# sc01a-breakout-board.net
KiCad netlist of a schematic drawn in EAGLE
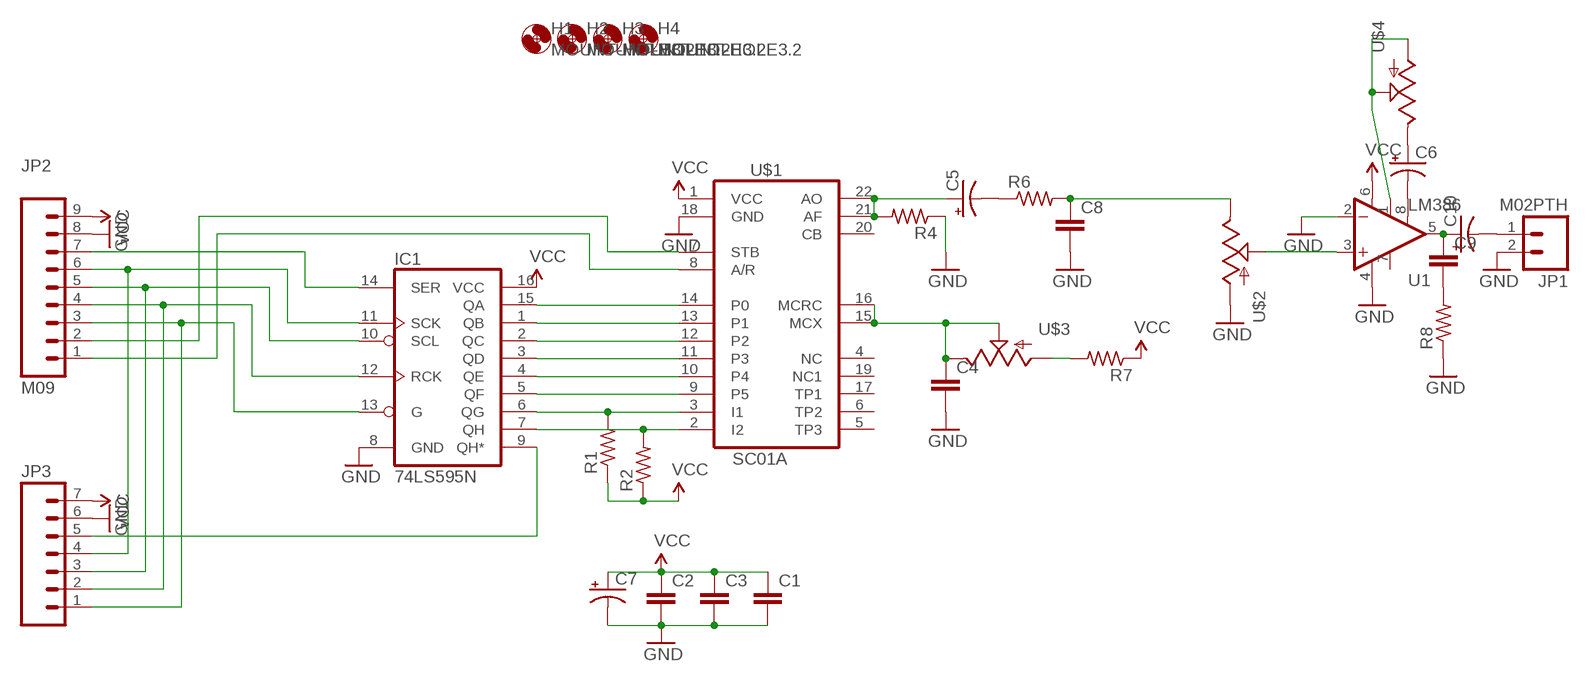
[diagram p0: schematic, sheet 1]

(export (version "E")
  (design (tool "Eeschema 10.0.6"))
  (components
    (comp (ref "C1")
      (value "CAPEZ")
      (footprint "eagle-import:CAP-PTH-SMALLEZ")
      (libsource (lib "eagle-import") (part "CAPEZ"))
    )
    (comp (ref "C2")
      (value "CAPEZ")
      (footprint "eagle-import:CAP-PTH-SMALLEZ")
      (libsource (lib "eagle-import") (part "CAPEZ"))
    )
    (comp (ref "C3")
      (value "CAPEZ")
      (footprint "eagle-import:CAP-PTH-SMALLEZ")
      (libsource (lib "eagle-import") (part "CAPEZ"))
    )
    (comp (ref "C4")
      (value "CAPEZ")
      (footprint "eagle-import:CAP-PTH-SMALLEZ")
      (libsource (lib "eagle-import") (part "CAPEZ"))
    )
    (comp (ref "C5")
      (value "CAP_POLPTH2")
      (footprint "eagle-import:CPOL-RADIAL-10UF-25V")
      (libsource (lib "eagle-import") (part "CAP_POLPTH2"))
    )
    (comp (ref "C6")
      (value "CAP_POLPTH2")
      (footprint "eagle-import:CPOL-RADIAL-10UF-25V")
      (libsource (lib "eagle-import") (part "CAP_POLPTH2"))
    )
    (comp (ref "C7")
      (value "CAP_POLPTH2")
      (footprint "eagle-import:CPOL-RADIAL-10UF-25V")
      (libsource (lib "eagle-import") (part "CAP_POLPTH2"))
    )
    (comp (ref "C8")
      (value "CAPEZ")
      (footprint "eagle-import:CAP-PTH-SMALLEZ")
      (libsource (lib "eagle-import") (part "CAPEZ"))
    )
    (comp (ref "C9")
      (value "CAPEZ")
      (footprint "eagle-import:CAP-PTH-SMALLEZ")
      (libsource (lib "eagle-import") (part "CAPEZ"))
    )
    (comp (ref "C10")
      (value "CAP_POLPTH2")
      (footprint "eagle-import:CPOL-RADIAL-10UF-25V")
      (libsource (lib "eagle-import") (part "CAP_POLPTH2"))
    )
    (comp (ref "H1")
      (value "MOUNT-HOLE3.2")
      (footprint "eagle-import:3,2")
      (libsource (lib "eagle-import") (part "MOUNT-HOLE3.2"))
    )
    (comp (ref "H2")
      (value "MOUNT-HOLE3.2")
      (footprint "eagle-import:3,2")
      (libsource (lib "eagle-import") (part "MOUNT-HOLE3.2"))
    )
    (comp (ref "H3")
      (value "MOUNT-HOLE3.2")
      (footprint "eagle-import:3,2")
      (libsource (lib "eagle-import") (part "MOUNT-HOLE3.2"))
    )
    (comp (ref "H4")
      (value "MOUNT-HOLE3.2")
      (footprint "eagle-import:3,2")
      (libsource (lib "eagle-import") (part "MOUNT-HOLE3.2"))
    )
    (comp (ref "IC1")
      (value "74LS595N")
      (footprint "eagle-import:DIL16")
      (libsource (lib "eagle-import") (part "74595NLS"))
    )
    (comp (ref "JP1")
      (value "M02PTH")
      (footprint "eagle-import:1X02")
      (libsource (lib "eagle-import") (part "M02PTH"))
    )
    (comp (ref "JP2")
      (value "M09")
      (footprint "eagle-import:1X09")
      (libsource (lib "eagle-import") (part "M09"))
    )
    (comp (ref "JP3")
      (value "M07")
      (footprint "eagle-import:1X07")
      (libsource (lib "eagle-import") (part "M07"))
    )
    (comp (ref "R1")
      (value "R-US_0204/5")
      (footprint "eagle-import:0204_5")
      (libsource (lib "eagle-import") (part "R-US_0204/5"))
    )
    (comp (ref "R2")
      (value "R-US_0204/5")
      (footprint "eagle-import:0204_5")
      (libsource (lib "eagle-import") (part "R-US_0204/5"))
    )
    (comp (ref "R4")
      (value "R-US_0204/5")
      (footprint "eagle-import:0204_5")
      (libsource (lib "eagle-import") (part "R-US_0204/5"))
    )
    (comp (ref "R6")
      (value "R-US_0204/5")
      (footprint "eagle-import:0204_5")
      (libsource (lib "eagle-import") (part "R-US_0204/5"))
    )
    (comp (ref "R7")
      (value "R-US_0204/5")
      (footprint "eagle-import:0204_5")
      (libsource (lib "eagle-import") (part "R-US_0204/5"))
    )
    (comp (ref "R8")
      (value "R-US_0204/5")
      (footprint "eagle-import:0204_5")
      (libsource (lib "eagle-import") (part "R-US_0204/5"))
    )
    (comp (ref "U$1")
      (value "SC01A")
      (footprint "eagle-import:22PDIP4")
      (libsource (lib "eagle-import") (part "SC01A"))
    )
    (comp (ref "U$2")
      (value "POTTRIM")
      (footprint "eagle-import:TRIM_POT")
      (libsource (lib "eagle-import") (part "POTTRIM"))
    )
    (comp (ref "U$3")
      (value "POTTRIM")
      (footprint "eagle-import:TRIM_POT")
      (libsource (lib "eagle-import") (part "POTTRIM"))
    )
    (comp (ref "U$4")
      (value "POTTRIM")
      (footprint "eagle-import:TRIM_POT")
      (libsource (lib "eagle-import") (part "POTTRIM"))
    )
    (comp (ref "U1")
      (value "LM386")
      (footprint "eagle-import:DIP08")
      (libsource (lib "eagle-import") (part "LM386"))
    )
  )
  (nets
    (net (code "1") (name "GND") (class "Default")
      (node (ref "C1") (pin "2") (pinfunction "2_2") (pintype "passive"))
      (node (ref "C2") (pin "2") (pinfunction "2_2") (pintype "passive"))
      (node (ref "C3") (pin "2") (pinfunction "2_2") (pintype "passive"))
      (node (ref "C4") (pin "2") (pinfunction "2_2") (pintype "passive"))
      (node (ref "C7") (pin "2") (pinfunction "-_2") (pintype "passive"))
      (node (ref "C8") (pin "2") (pinfunction "2_2") (pintype "passive"))
      (node (ref "IC1") (pin "8") (pinfunction "GND_8") (pintype "power_in"))
      (node (ref "JP1") (pin "2") (pinfunction "2_2") (pintype "passive"))
      (node (ref "JP2") (pin "8") (pinfunction "8_8") (pintype "passive"))
      (node (ref "JP3") (pin "6") (pinfunction "6_6") (pintype "passive"))
      (node (ref "R4") (pin "1") (pinfunction "1_1") (pintype "passive"))
      (node (ref "R8") (pin "1") (pinfunction "1_1") (pintype "passive"))
      (node (ref "U$1") (pin "18") (pinfunction "GND_18") (pintype "power_in"))
      (node (ref "U$2") (pin "3") (pinfunction "A_3") (pintype "passive"))
      (node (ref "U1") (pin "2") (pinfunction "-IN_2") (pintype "input"))
      (node (ref "U1") (pin "4") (pinfunction "V-_4") (pintype "power_in"))
    )
    (net (code "2") (name "Net-(C5-+)") (class "Default")
      (node (ref "C5") (pin "1") (pinfunction "+_1") (pintype "passive"))
      (node (ref "R4") (pin "2") (pinfunction "2_2") (pintype "passive"))
      (node (ref "U$1") (pin "21") (pinfunction "AF_21") (pintype "output"))
      (node (ref "U$1") (pin "22") (pinfunction "AO_22") (pintype "output"))
    )
    (net (code "3") (name "Net-(C5--)") (class "Default")
      (node (ref "C5") (pin "2") (pinfunction "-_2") (pintype "passive"))
      (node (ref "R6") (pin "1") (pinfunction "1_1") (pintype "passive"))
    )
    (net (code "4") (name "Net-(C6-+)") (class "Default")
      (node (ref "C6") (pin "1") (pinfunction "+_1") (pintype "passive"))
      (node (ref "U$4") (pin "2") (pinfunction "E_2") (pintype "passive"))
    )
    (net (code "5") (name "Net-(C6--)") (class "Default")
      (node (ref "C6") (pin "2") (pinfunction "-_2") (pintype "passive"))
      (node (ref "U1") (pin "8") (pinfunction "GAIN_8") (pintype "bidirectional"))
    )
    (net (code "6") (name "Net-(C9-Pad2)") (class "Default")
      (node (ref "C9") (pin "2") (pinfunction "2_2") (pintype "passive"))
      (node (ref "R8") (pin "2") (pinfunction "2_2") (pintype "passive"))
    )
    (net (code "7") (name "Net-(C10-+)") (class "Default")
      (node (ref "C10") (pin "1") (pinfunction "+_1") (pintype "passive"))
      (node (ref "C9") (pin "1") (pinfunction "1_1") (pintype "passive"))
      (node (ref "U1") (pin "5") (pinfunction "OUT_5") (pintype "output"))
    )
    (net (code "8") (name "Net-(C10--)") (class "Default")
      (node (ref "C10") (pin "2") (pinfunction "-_2") (pintype "passive"))
      (node (ref "JP1") (pin "1") (pinfunction "1_1") (pintype "passive"))
    )
    (net (code "9") (name "Net-(IC1-G)") (class "Default")
      (node (ref "IC1") (pin "13") (pinfunction "G_13") (pintype "input"))
      (node (ref "JP2") (pin "3") (pinfunction "3_3") (pintype "passive"))
      (node (ref "JP3") (pin "1") (pinfunction "1_1") (pintype "passive"))
    )
    (net (code "10") (name "Net-(IC1-QA)") (class "Default")
      (node (ref "IC1") (pin "15") (pinfunction "QA_15") (pintype "tri_state"))
      (node (ref "U$1") (pin "14") (pinfunction "P0_14") (pintype "input"))
    )
    (net (code "11") (name "Net-(IC1-QB)") (class "Default")
      (node (ref "IC1") (pin "1") (pinfunction "QB_1") (pintype "tri_state"))
      (node (ref "U$1") (pin "13") (pinfunction "P1_13") (pintype "input"))
    )
    (net (code "12") (name "Net-(IC1-QC)") (class "Default")
      (node (ref "IC1") (pin "2") (pinfunction "QC_2") (pintype "tri_state"))
      (node (ref "U$1") (pin "12") (pinfunction "P2_12") (pintype "input"))
    )
    (net (code "13") (name "Net-(IC1-QD)") (class "Default")
      (node (ref "IC1") (pin "3") (pinfunction "QD_3") (pintype "tri_state"))
      (node (ref "U$1") (pin "11") (pinfunction "P3_11") (pintype "input"))
    )
    (net (code "14") (name "Net-(IC1-QE)") (class "Default")
      (node (ref "IC1") (pin "4") (pinfunction "QE_4") (pintype "tri_state"))
      (node (ref "U$1") (pin "10") (pinfunction "P4_10") (pintype "input"))
    )
    (net (code "15") (name "Net-(IC1-QF)") (class "Default")
      (node (ref "IC1") (pin "5") (pinfunction "QF_5") (pintype "tri_state"))
      (node (ref "U$1") (pin "9") (pinfunction "P5_9") (pintype "input"))
    )
    (net (code "16") (name "Net-(IC1-QG)") (class "Default")
      (node (ref "IC1") (pin "6") (pinfunction "QG_6") (pintype "tri_state"))
      (node (ref "R1") (pin "2") (pinfunction "2_2") (pintype "passive"))
      (node (ref "U$1") (pin "3") (pinfunction "I1_3") (pintype "input"))
    )
    (net (code "17") (name "Net-(IC1-QH)") (class "Default")
      (node (ref "IC1") (pin "7") (pinfunction "QH_7") (pintype "tri_state"))
      (node (ref "R2") (pin "2") (pinfunction "2_2") (pintype "passive"))
      (node (ref "U$1") (pin "2") (pinfunction "I2_2") (pintype "input"))
    )
    (net (code "18") (name "Net-(IC1-QH*)") (class "Default")
      (node (ref "IC1") (pin "9") (pinfunction "QH*_9") (pintype "tri_state"))
      (node (ref "JP3") (pin "5") (pinfunction "5_5") (pintype "passive"))
    )
    (net (code "19") (name "Net-(IC1-RCK)") (class "Default")
      (node (ref "IC1") (pin "12") (pinfunction "RCK_12") (pintype "input"))
      (node (ref "JP2") (pin "4") (pinfunction "4_4") (pintype "passive"))
      (node (ref "JP3") (pin "2") (pinfunction "2_2") (pintype "passive"))
    )
    (net (code "20") (name "Net-(IC1-SCK)") (class "Default")
      (node (ref "IC1") (pin "11") (pinfunction "SCK_11") (pintype "input"))
      (node (ref "JP2") (pin "6") (pinfunction "6_6") (pintype "passive"))
      (node (ref "JP3") (pin "4") (pinfunction "4_4") (pintype "passive"))
    )
    (net (code "21") (name "Net-(IC1-SCL)") (class "Default")
      (node (ref "IC1") (pin "10") (pinfunction "SCL_10") (pintype "input"))
      (node (ref "JP2") (pin "5") (pinfunction "5_5") (pintype "passive"))
      (node (ref "JP3") (pin "3") (pinfunction "3_3") (pintype "passive"))
    )
    (net (code "22") (name "Net-(IC1-SER)") (class "Default")
      (node (ref "IC1") (pin "14") (pinfunction "SER_14") (pintype "input"))
      (node (ref "JP2") (pin "7") (pinfunction "7_7") (pintype "passive"))
    )
    (net (code "23") (name "Net-(U$1-A{slash}R)") (class "Default")
      (node (ref "JP2") (pin "1") (pinfunction "1_1") (pintype "passive"))
      (node (ref "U$1") (pin "8") (pinfunction "A/R_8") (pintype "output"))
    )
    (net (code "24") (name "Net-(U$1-MCRC)") (class "Default")
      (node (ref "C4") (pin "1") (pinfunction "1_1") (pintype "passive"))
      (node (ref "U$1") (pin "15") (pinfunction "MCX_15") (pintype "input"))
      (node (ref "U$1") (pin "16") (pinfunction "MCRC_16") (pintype "input"))
      (node (ref "U$3") (pin "1") (pinfunction "S_1") (pintype "passive"))
      (node (ref "U$3") (pin "2") (pinfunction "E_2") (pintype "passive"))
    )
    (net (code "25") (name "Net-(U$1-STB)") (class "Default")
      (node (ref "JP2") (pin "2") (pinfunction "2_2") (pintype "passive"))
      (node (ref "U$1") (pin "7") (pinfunction "STB_7") (pintype "input"))
    )
    (net (code "26") (name "Net-(U$2-E)") (class "Default")
      (node (ref "C8") (pin "1") (pinfunction "1_1") (pintype "passive"))
      (node (ref "R6") (pin "2") (pinfunction "2_2") (pintype "passive"))
      (node (ref "U$2") (pin "2") (pinfunction "E_2") (pintype "passive"))
    )
    (net (code "27") (name "Net-(U$2-S)") (class "Default")
      (node (ref "U$2") (pin "1") (pinfunction "S_1") (pintype "passive"))
      (node (ref "U1") (pin "3") (pinfunction "+IN_3") (pintype "input"))
    )
    (net (code "28") (name "Net-(U$3-A)") (class "Default")
      (node (ref "R7") (pin "2") (pinfunction "2_2") (pintype "passive"))
      (node (ref "U$3") (pin "3") (pinfunction "A_3") (pintype "passive"))
    )
    (net (code "29") (name "Net-(U$4-A)") (class "Default")
      (node (ref "U$4") (pin "1") (pinfunction "S_1") (pintype "passive"))
      (node (ref "U$4") (pin "3") (pinfunction "A_3") (pintype "passive"))
      (node (ref "U1") (pin "1") (pinfunction "GAIN_1") (pintype "bidirectional"))
    )
    (net (code "30") (name "VCC") (class "Default")
      (node (ref "C1") (pin "1") (pinfunction "1_1") (pintype "passive"))
      (node (ref "C2") (pin "1") (pinfunction "1_1") (pintype "passive"))
      (node (ref "C3") (pin "1") (pinfunction "1_1") (pintype "passive"))
      (node (ref "C7") (pin "1") (pinfunction "+_1") (pintype "passive"))
      (node (ref "IC1") (pin "16") (pinfunction "VCC_16") (pintype "power_in"))
      (node (ref "JP2") (pin "9") (pinfunction "9_9") (pintype "passive"))
      (node (ref "JP3") (pin "7") (pinfunction "7_7") (pintype "passive"))
      (node (ref "R1") (pin "1") (pinfunction "1_1") (pintype "passive"))
      (node (ref "R2") (pin "1") (pinfunction "1_1") (pintype "passive"))
      (node (ref "R7") (pin "1") (pinfunction "1_1") (pintype "passive"))
      (node (ref "U$1") (pin "1") (pinfunction "VCC_1") (pintype "power_in"))
      (node (ref "U1") (pin "6") (pinfunction "V+_6") (pintype "power_in"))
    )
    (net (code "31") (name "unconnected-(U$1-CB-Pad20)") (class "Default")
      (node (ref "U$1") (pin "20") (pinfunction "CB_20") (pintype "output"))
    )
    (net (code "32") (name "unconnected-(U$1-NC-Pad4)") (class "Default")
      (node (ref "U$1") (pin "4") (pinfunction "NC_4") (pintype "no_connect"))
    )
    (net (code "33") (name "unconnected-(U$1-NC1-Pad19)") (class "Default")
      (node (ref "U$1") (pin "19") (pinfunction "NC1_19") (pintype "no_connect"))
    )
    (net (code "34") (name "unconnected-(U$1-TP1-Pad17)") (class "Default")
      (node (ref "U$1") (pin "17") (pinfunction "TP1_17") (pintype "no_connect"))
    )
    (net (code "35") (name "unconnected-(U$1-TP2-Pad6)") (class "Default")
      (node (ref "U$1") (pin "6") (pinfunction "TP2_6") (pintype "no_connect"))
    )
    (net (code "36") (name "unconnected-(U$1-TP3-Pad5)") (class "Default")
      (node (ref "U$1") (pin "5") (pinfunction "TP3_5") (pintype "no_connect"))
    )
    (net (code "37") (name "unconnected-(U1-BP-Pad7)") (class "Default")
      (node (ref "U1") (pin "7") (pinfunction "BP_7") (pintype "bidirectional"))
    )
  )
)
